# Module_A_IO.net
KiCad netlist of a schematic drawn in Altium Designer
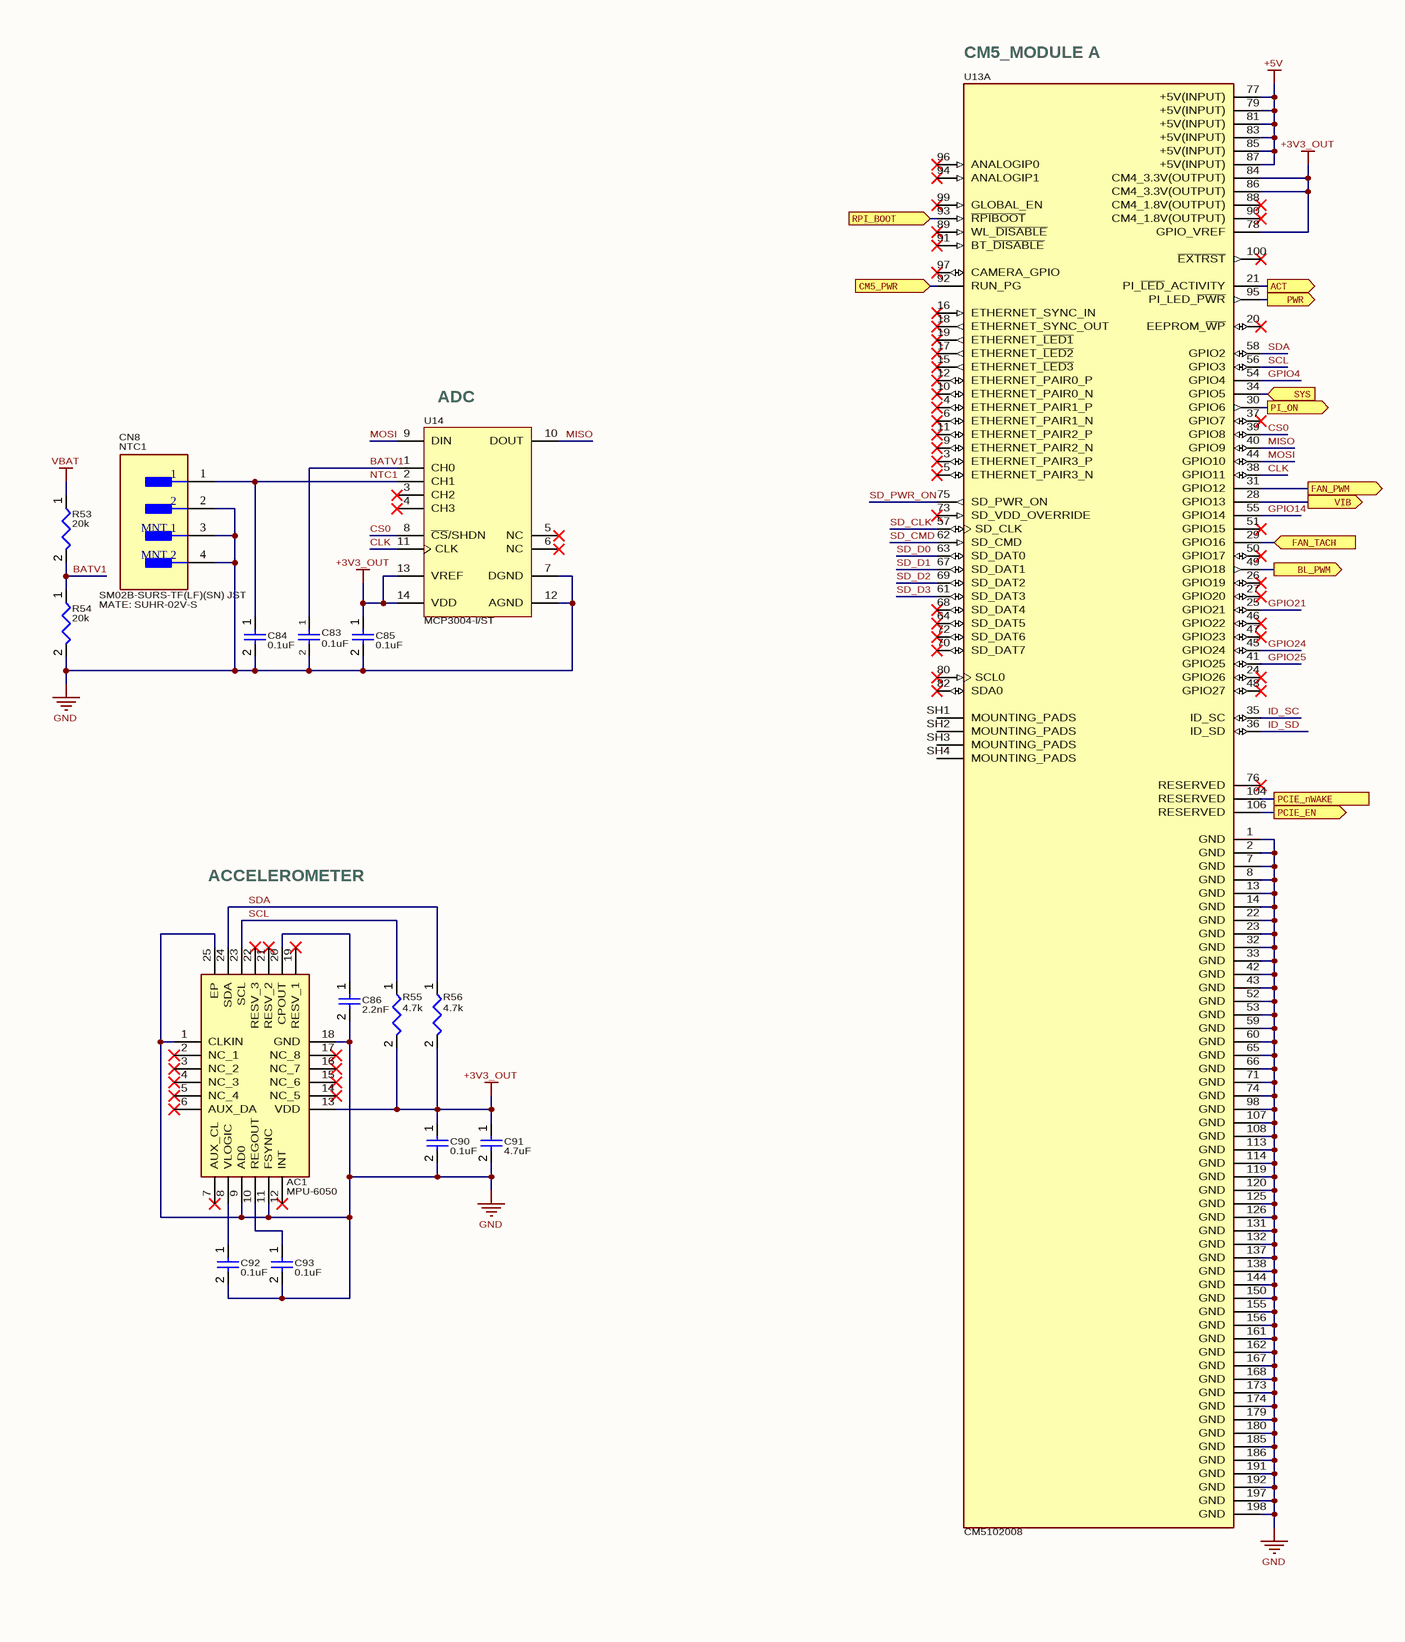
[diagram p0: Module A IO.SchDoc, left]
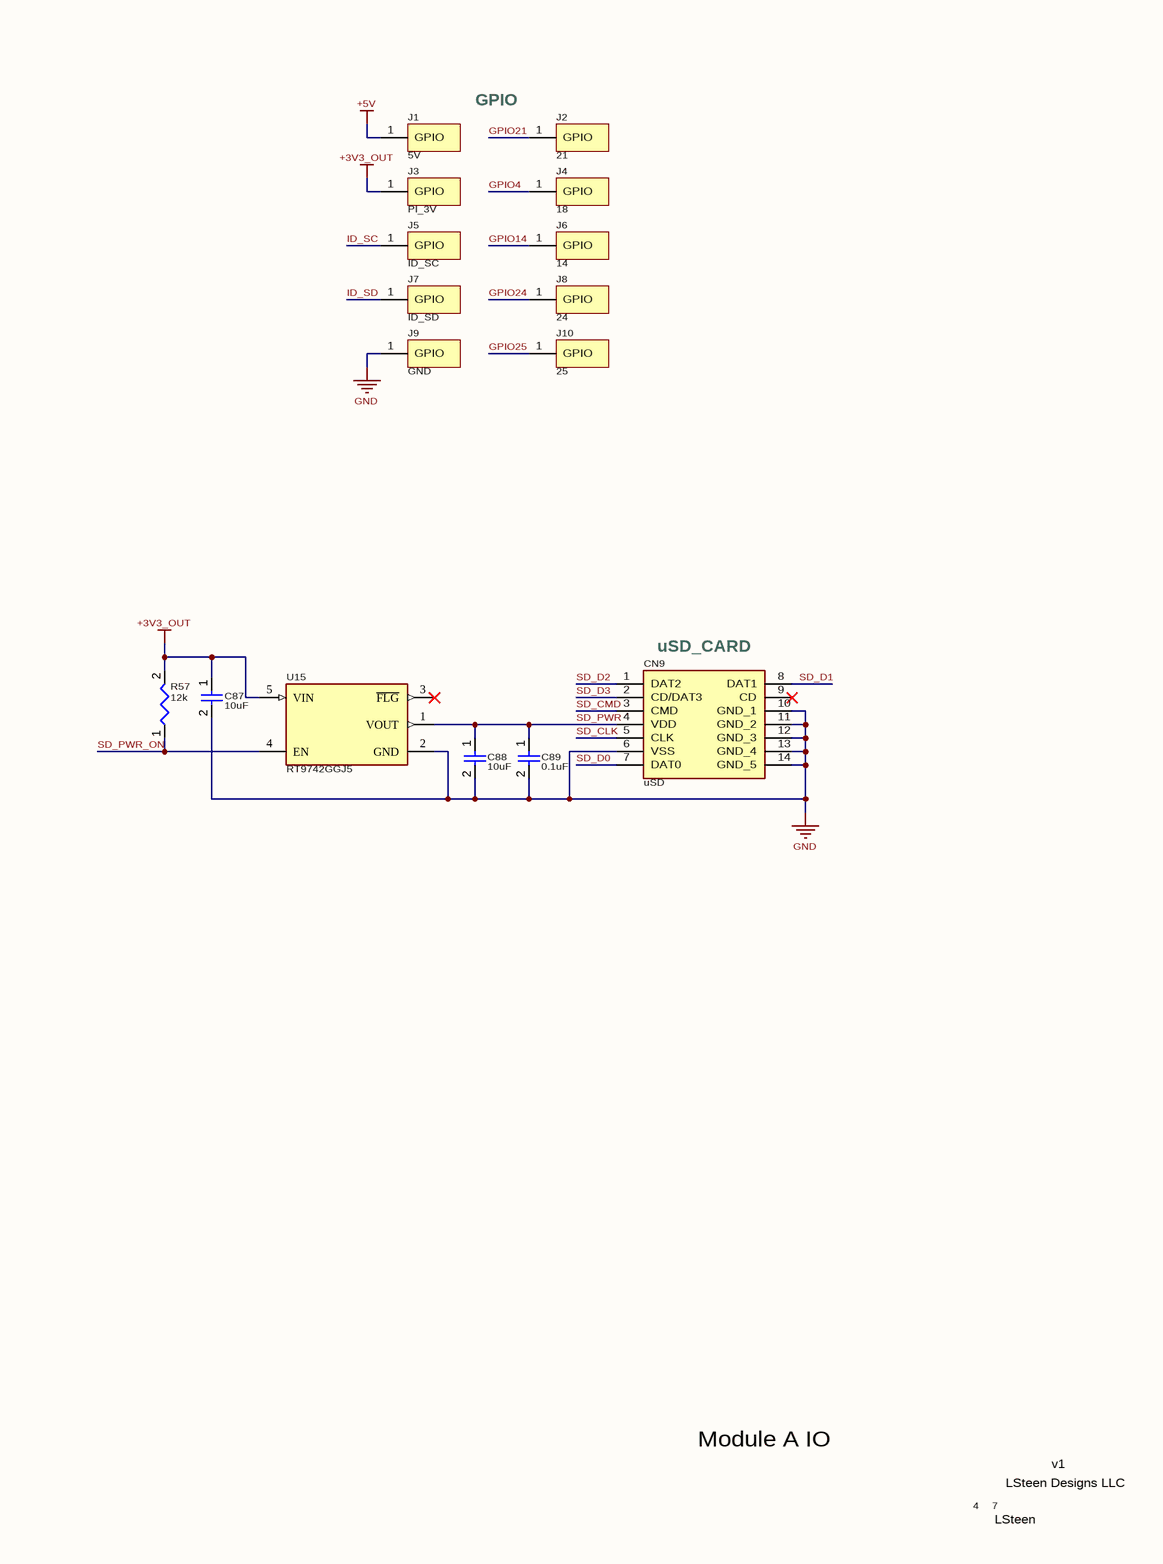
[diagram p1: Module A IO.SchDoc, right]

(export (version "E")
  (design (tool "Eeschema 10.0.6"))
  (components
    (comp (ref "AC1")
      (value "MPU-6050")
      (footprint "SamacSys:MPU6050")
      (description "Integrated Circuit")
      (fields (field (name "MOUSER PART NUMBER") "410-MPU-6050"))
      (libsource (lib "SamacSys") (part "MPU-6050"))
    )
    (comp (ref "C83")
      (value "0.1uF")
      (footprint "SamacSys:CAPC1005X55N")
      (description "C0402")
      (libsource (lib "SamacSys") (part "C0402"))
    )
    (comp (ref "C84")
      (value "0.1uF")
      (footprint "CAPC1005X56X25LL10T15")
      (description "Chip Capacitor, 0.1 uF, +/- 5%, 16 V, 0402 (1005 Metric)")
      (fields (field (name "TOLERANCE") "5%"))
      (libsource (lib "Colorado Technical University") (part "CAP-NP-2"))
    )
    (comp (ref "C85")
      (value "0.1uF")
      (footprint "CAPC1005X56X25LL10T15")
      (description "Chip Capacitor, 0.1 uF, +/- 5%, 16 V, 0402 (1005 Metric)")
      (fields (field (name "TOLERANCE") "5%"))
      (libsource (lib "Colorado Technical University") (part "CAP-NP-2"))
    )
    (comp (ref "C86")
      (value "2.2nF")
      (footprint "CAPC1005X56X25LL10T15")
      (description "Chip Capacitor, 2.2nF, +/- 5%, 16 V, 0402 (1005 Metric)")
      (fields (field (name "TOLERANCE") "5%"))
      (libsource (lib "Colorado Technical University") (part "CAP-NP-2"))
    )
    (comp (ref "C87")
      (value "10uF")
      (footprint "CAPC0603(1608)100_L")
      (description "Chip Capacitor, 10uF +/-20%, 10V, 0603, Thickness 1 mm")
      (fields (field (name "TOLERANCE") "10%"))
      (libsource (lib "Colorado Technical University") (part "CAP-NP-2"))
    )
    (comp (ref "C88")
      (value "10uF")
      (footprint "CAPC0603(1608)100_L")
      (description "Chip Capacitor, 10uF +/-20%, 10V, 0603, Thickness 1 mm")
      (fields (field (name "TOLERANCE") "10%"))
      (libsource (lib "Colorado Technical University") (part "CAP-NP-2"))
    )
    (comp (ref "C89")
      (value "0.1uF")
      (footprint "CAPC1005X56X25LL10T15")
      (description "Chip Capacitor, 0.1 uF, +/- 5%, 16 V, 0402 (1005 Metric)")
      (fields (field (name "TOLERANCE") "5%"))
      (libsource (lib "Colorado Technical University") (part "CAP-NP-2"))
    )
    (comp (ref "C90")
      (value "0.1uF")
      (footprint "CAPC1005X56X25LL10T15")
      (description "Chip Capacitor, 0.1 uF, +/- 5%, 16 V, 0402 (1005 Metric)")
      (fields (field (name "TOLERANCE") "5%"))
      (libsource (lib "Colorado Technical University") (part "CAP-NP-2"))
    )
    (comp (ref "C91")
      (value "4.7uF")
      (footprint "CAPC0603(1608)100_L")
      (description "Chip Capacitor, 4.7uF +/-20%, 10V, 0603, Thickness 1 mm")
      (fields (field (name "TOLERANCE") "10%"))
      (libsource (lib "Colorado Technical University") (part "CAP-NP-2"))
    )
    (comp (ref "C92")
      (value "0.1uF")
      (footprint "CAPC1005X56X25LL10T15")
      (description "Chip Capacitor, 0.1 uF, +/- 5%, 16 V, 0402 (1005 Metric)")
      (fields (field (name "TOLERANCE") "5%"))
      (libsource (lib "Colorado Technical University") (part "CAP-NP-2"))
    )
    (comp (ref "C93")
      (value "0.1uF")
      (footprint "CAPC1005X56X25LL10T15")
      (description "Chip Capacitor, 0.1 uF, +/- 5%, 16 V, 0402 (1005 Metric)")
      (fields (field (name "TOLERANCE") "5%"))
      (libsource (lib "Colorado Technical University") (part "CAP-NP-2"))
    )
    (comp (ref "CN8")
      (value "NTC1")
      (footprint "FP-SM02B-SURS-TF_LF_SN-MFG")
      (description "LCSC_CONN HEADER SMD R/A 2POS 0.8MM")
      (libsource (lib "Altium Content Vault") (part "6ebc6fc72a9fd5a6899c7600f385cff"))
    )
    (comp (ref "CN9")
      (value "uSD")
      (footprint "SamacSys:MSD9A")
      (description "Connector")
      (fields (field (name "MANUFACTURER_PART_NUMBER") "MSD-9-A"))
      (libsource (lib "SamacSys") (part "MSD-9-A"))
    )
    (comp (ref "J1")
      (value "5V")
      (footprint "GPIO")
      (description "AUX_I/O")
      (libsource (lib "Schlib1") (part "GPIO"))
    )
    (comp (ref "J2")
      (value "21")
      (footprint "GPIO")
      (description "AUX_I/O")
      (libsource (lib "Schlib1") (part "GPIO"))
    )
    (comp (ref "J3")
      (value "PI_3V")
      (footprint "GPIO")
      (description "AUX_I/O")
      (libsource (lib "Schlib1") (part "GPIO"))
    )
    (comp (ref "J4")
      (value "18")
      (footprint "GPIO")
      (description "AUX_I/O")
      (libsource (lib "Schlib1") (part "GPIO"))
    )
    (comp (ref "J5")
      (value "ID_SC")
      (footprint "GPIO")
      (description "AUX_I/O")
      (libsource (lib "Schlib1") (part "GPIO"))
    )
    (comp (ref "J6")
      (value "14")
      (footprint "GPIO")
      (description "AUX_I/O")
      (libsource (lib "Schlib1") (part "GPIO"))
    )
    (comp (ref "J7")
      (value "ID_SD")
      (footprint "GPIO")
      (description "AUX_I/O")
      (libsource (lib "Schlib1") (part "GPIO"))
    )
    (comp (ref "J8")
      (value "24")
      (footprint "GPIO")
      (description "AUX_I/O")
      (libsource (lib "Schlib1") (part "GPIO"))
    )
    (comp (ref "J9")
      (value "GND")
      (footprint "GPIO")
      (description "AUX_I/O")
      (libsource (lib "Schlib1") (part "GPIO"))
    )
    (comp (ref "J10")
      (value "25")
      (footprint "GPIO")
      (description "AUX_I/O")
      (libsource (lib "Schlib1") (part "GPIO"))
    )
    (comp (ref "R53")
      (value "20k")
      (footprint "RESC0402(1005)_L")
      (description "Chip Resistor, 20 kOhms, +/-5 %, 63 mW, -55 to 155 degC, 0402")
      (fields (field (name "TOLERANCE") "5%") (field (name "POWER") "63mW"))
      (libsource (lib "Colorado Technical University") (part "RES-2"))
    )
    (comp (ref "R54")
      (value "20k")
      (footprint "RESC0402(1005)_L")
      (description "Chip Resistor, 20 kOhms, +/-5 %, 63 mW, -55 to 155 degC, 0402")
      (fields (field (name "TOLERANCE") "5%") (field (name "POWER") "63mW"))
      (libsource (lib "Colorado Technical University") (part "RES-2"))
    )
    (comp (ref "R55")
      (value "4.7k")
      (footprint "RESC0402(1005)_L")
      (description "Chip Resistor, 4.7 kOhms, +/-5 %, 63 mW, -55 to 155 degC, 0402")
      (fields (field (name "TOLERANCE") "5%") (field (name "POWER") "63mW"))
      (libsource (lib "Colorado Technical University") (part "RES-2"))
    )
    (comp (ref "R56")
      (value "4.7k")
      (footprint "RESC0402(1005)_L")
      (description "Chip Resistor, 4.7 kOhms, +/-5 %, 63 mW, -55 to 155 degC, 0402")
      (fields (field (name "TOLERANCE") "5%") (field (name "POWER") "63mW"))
      (libsource (lib "Colorado Technical University") (part "RES-2"))
    )
    (comp (ref "R57")
      (value "12k")
      (footprint "RESC0402(1005)_L")
      (description "Chip Resistor, 12 kOhms, +/-5 %, 63 mW, -55 to 155 degC, 0402")
      (fields (field (name "TOLERANCE") "5%") (field (name "POWER") "63mW"))
      (libsource (lib "Colorado Technical University") (part "RES-2"))
    )
    (comp (ref "U13")
      (value "CM5102008")
      (footprint "MODULE_CM4102008")
      (description "Raspberry Pi Compute Module 4 with WiFi 2GB RAM 8GB Flash ¦ Raspberry Pi CM4102008")
      (fields (field (name "MF") "Raspberry Pi") (field (name "MP") "CM4102008"))
      (libsource (lib "CM4102008") (part "CM4102008"))
    )
    (comp (ref "U14")
      (value "MCP3004-I/ST")
      (footprint "TSSOP-ST14_M")
      (libsource (lib "Altium Content Vault") (part "CON-ADC-MCP3004-14"))
    )
    (comp (ref "U15")
      (value "RT9742GGJ5")
      (footprint "FP-RT9742GGJ5-IPC_C")
      (description "IC PWR SWTCH N-CHAN 1:1 TSOT23-5")
      (libsource (lib "Altium Content Vault") (part "6b3db7b45087fee8fb60b49bef92a32"))
    )
  )
  (nets
    (net (code "1") (name "+3V3_OUT") (class "Default")
      (node (ref "AC1") (pin "13") (pinfunction "VDD_13") (pintype "passive"))
      (node (ref "C85") (pin "1") (pinfunction "1_1") (pintype "passive"))
      (node (ref "C87") (pin "1") (pinfunction "1_1") (pintype "passive"))
      (node (ref "C90") (pin "1") (pinfunction "1_1") (pintype "passive"))
      (node (ref "C91") (pin "1") (pinfunction "1_1") (pintype "passive"))
      (node (ref "J3") (pin "1") (pinfunction "GPIO_1") (pintype "passive"))
      (node (ref "R55") (pin "2") (pinfunction "2_2") (pintype "passive"))
      (node (ref "R56") (pin "2") (pinfunction "2_2") (pintype "passive"))
      (node (ref "R57") (pin "2") (pinfunction "2_2") (pintype "passive"))
      (node (ref "U13") (pin "78") (pinfunction "GPIO_VREF_78") (pintype "power_in"))
      (node (ref "U13") (pin "84") (pinfunction "CM4_3.3V(OUTPUT)_84") (pintype "power_in"))
      (node (ref "U13") (pin "86") (pinfunction "CM4_3.3V(OUTPUT)_86") (pintype "power_in"))
      (node (ref "U14") (pin "13") (pinfunction "VREF_13") (pintype "passive"))
      (node (ref "U14") (pin "14") (pinfunction "VDD_14") (pintype "power_in"))
      (node (ref "U15") (pin "5") (pinfunction "VIN_5") (pintype "input"))
    )
    (net (code "2") (name "+5V") (class "Default")
      (node (ref "J1") (pin "1") (pinfunction "GPIO_1") (pintype "passive"))
      (node (ref "U13") (pin "77") (pinfunction "+5V(INPUT)_77") (pintype "power_in"))
      (node (ref "U13") (pin "79") (pinfunction "+5V(INPUT)_79") (pintype "power_in"))
      (node (ref "U13") (pin "81") (pinfunction "+5V(INPUT)_81") (pintype "power_in"))
      (node (ref "U13") (pin "83") (pinfunction "+5V(INPUT)_83") (pintype "power_in"))
      (node (ref "U13") (pin "85") (pinfunction "+5V(INPUT)_85") (pintype "power_in"))
      (node (ref "U13") (pin "87") (pinfunction "+5V(INPUT)_87") (pintype "power_in"))
    )
    (net (code "3") (name "/ACT") (class "Default")
      (node (ref "U13") (pin "21") (pinfunction "PI_~{LED}_ACTIVITY_21") (pintype "passive"))
    )
    (net (code "4") (name "/BATV1") (class "Default")
      (node (ref "C83") (pin "1") (pinfunction "1_1") (pintype "passive"))
      (node (ref "R53") (pin "2") (pinfunction "2_2") (pintype "passive"))
      (node (ref "R54") (pin "1") (pinfunction "1_1") (pintype "passive"))
      (node (ref "U14") (pin "1") (pinfunction "CH0_1") (pintype "passive"))
    )
    (net (code "5") (name "/BL_PWM") (class "Default")
      (node (ref "U13") (pin "49") (pinfunction "GPIO18_49") (pintype "output"))
    )
    (net (code "6") (name "/CLK") (class "Default")
      (node (ref "U13") (pin "38") (pinfunction "GPIO11_38") (pintype "bidirectional"))
      (node (ref "U14") (pin "11") (pinfunction "CLK_11") (pintype "passive"))
    )
    (net (code "7") (name "/CM5_PWR") (class "Default")
      (node (ref "U13") (pin "92") (pinfunction "RUN_PG_92") (pintype "passive"))
    )
    (net (code "8") (name "/CS0") (class "Default")
      (node (ref "U13") (pin "39") (pinfunction "GPIO8_39") (pintype "bidirectional"))
      (node (ref "U14") (pin "8") (pinfunction "~{CS}/SHDN_8") (pintype "passive"))
    )
    (net (code "9") (name "/FAN_PWM") (class "Default")
      (node (ref "U13") (pin "31") (pinfunction "GPIO12_31") (pintype "passive"))
    )
    (net (code "10") (name "/FAN_TACH") (class "Default")
      (node (ref "U13") (pin "29") (pinfunction "GPIO16_29") (pintype "passive"))
    )
    (net (code "11") (name "/GPIO4") (class "Default")
      (node (ref "J4") (pin "1") (pinfunction "GPIO_1") (pintype "passive"))
      (node (ref "U13") (pin "54") (pinfunction "GPIO4_54") (pintype "passive"))
    )
    (net (code "12") (name "/GPIO14") (class "Default")
      (node (ref "J6") (pin "1") (pinfunction "GPIO_1") (pintype "passive"))
      (node (ref "U13") (pin "55") (pinfunction "GPIO14_55") (pintype "passive"))
    )
    (net (code "13") (name "/GPIO21") (class "Default")
      (node (ref "J2") (pin "1") (pinfunction "GPIO_1") (pintype "passive"))
      (node (ref "U13") (pin "25") (pinfunction "GPIO21_25") (pintype "bidirectional"))
    )
    (net (code "14") (name "/GPIO24") (class "Default")
      (node (ref "J8") (pin "1") (pinfunction "GPIO_1") (pintype "passive"))
      (node (ref "U13") (pin "45") (pinfunction "GPIO24_45") (pintype "bidirectional"))
    )
    (net (code "15") (name "/GPIO25") (class "Default")
      (node (ref "J10") (pin "1") (pinfunction "GPIO_1") (pintype "passive"))
      (node (ref "U13") (pin "41") (pinfunction "GPIO25_41") (pintype "bidirectional"))
    )
    (net (code "16") (name "/ID_SC") (class "Default")
      (node (ref "J5") (pin "1") (pinfunction "GPIO_1") (pintype "passive"))
      (node (ref "U13") (pin "35") (pinfunction "ID_SC_35") (pintype "bidirectional"))
    )
    (net (code "17") (name "/ID_SD") (class "Default")
      (node (ref "J7") (pin "1") (pinfunction "GPIO_1") (pintype "passive"))
      (node (ref "U13") (pin "36") (pinfunction "ID_SD_36") (pintype "bidirectional"))
    )
    (net (code "18") (name "/MISO") (class "Default")
      (node (ref "U13") (pin "40") (pinfunction "GPIO9_40") (pintype "bidirectional"))
      (node (ref "U14") (pin "10") (pinfunction "DOUT_10") (pintype "tri_state"))
    )
    (net (code "19") (name "/MOSI") (class "Default")
      (node (ref "U13") (pin "44") (pinfunction "GPIO10_44") (pintype "bidirectional"))
      (node (ref "U14") (pin "9") (pinfunction "DIN_9") (pintype "passive"))
    )
    (net (code "20") (name "/NTC1") (class "Default")
      (node (ref "C84") (pin "1") (pinfunction "1_1") (pintype "passive"))
      (node (ref "CN8") (pin "1") (pinfunction "1_1") (pintype "passive"))
      (node (ref "U14") (pin "2") (pinfunction "CH1_2") (pintype "passive"))
    )
    (net (code "21") (name "/PCIE_EN") (class "Default")
      (node (ref "U13") (pin "106") (pinfunction "RESERVED_106") (pintype "passive"))
    )
    (net (code "22") (name "/PCIE_nWAKE") (class "Default")
      (node (ref "U13") (pin "104") (pinfunction "RESERVED_104") (pintype "passive"))
    )
    (net (code "23") (name "/PI_ON") (class "Default")
      (node (ref "U13") (pin "30") (pinfunction "GPIO6_30") (pintype "output"))
    )
    (net (code "24") (name "/PWR") (class "Default")
      (node (ref "U13") (pin "95") (pinfunction "PI_LED_~{PWR}_95") (pintype "output"))
    )
    (net (code "25") (name "/RPI_BOOT") (class "Default")
      (node (ref "U13") (pin "93") (pinfunction "~{RPIBOOT}_93") (pintype "input"))
    )
    (net (code "26") (name "/SCL") (class "Default")
      (node (ref "AC1") (pin "23") (pinfunction "SCL_23") (pintype "passive"))
      (node (ref "R55") (pin "1") (pinfunction "1_1") (pintype "passive"))
      (node (ref "U13") (pin "56") (pinfunction "GPIO3_56") (pintype "bidirectional"))
    )
    (net (code "27") (name "/SDA") (class "Default")
      (node (ref "AC1") (pin "24") (pinfunction "SDA_24") (pintype "passive"))
      (node (ref "R56") (pin "1") (pinfunction "1_1") (pintype "passive"))
      (node (ref "U13") (pin "58") (pinfunction "GPIO2_58") (pintype "bidirectional"))
    )
    (net (code "28") (name "/SD_CLK") (class "Default")
      (node (ref "CN9") (pin "5") (pinfunction "CLK_5") (pintype "passive"))
      (node (ref "U13") (pin "57") (pinfunction "SD_CLK_57") (pintype "bidirectional"))
    )
    (net (code "29") (name "/SD_CMD") (class "Default")
      (node (ref "CN9") (pin "3") (pinfunction "CMD_3") (pintype "passive"))
      (node (ref "U13") (pin "62") (pinfunction "SD_CMD_62") (pintype "input"))
    )
    (net (code "30") (name "/SD_D0") (class "Default")
      (node (ref "CN9") (pin "7") (pinfunction "DAT0_7") (pintype "passive"))
      (node (ref "U13") (pin "63") (pinfunction "SD_DAT0_63") (pintype "bidirectional"))
    )
    (net (code "31") (name "/SD_D1") (class "Default")
      (node (ref "CN9") (pin "8") (pinfunction "DAT1_8") (pintype "passive"))
      (node (ref "U13") (pin "67") (pinfunction "SD_DAT1_67") (pintype "bidirectional"))
    )
    (net (code "32") (name "/SD_D2") (class "Default")
      (node (ref "CN9") (pin "1") (pinfunction "DAT2_1") (pintype "passive"))
      (node (ref "U13") (pin "69") (pinfunction "SD_DAT2_69") (pintype "bidirectional"))
    )
    (net (code "33") (name "/SD_D3") (class "Default")
      (node (ref "CN9") (pin "2") (pinfunction "CD/DAT3_2") (pintype "passive"))
      (node (ref "U13") (pin "61") (pinfunction "SD_DAT3_61") (pintype "bidirectional"))
    )
    (net (code "34") (name "/SD_PWR") (class "Default")
      (node (ref "C88") (pin "1") (pinfunction "1_1") (pintype "passive"))
      (node (ref "C89") (pin "1") (pinfunction "1_1") (pintype "passive"))
      (node (ref "CN9") (pin "4") (pinfunction "VDD_4") (pintype "passive"))
      (node (ref "U15") (pin "1") (pinfunction "VOUT_1") (pintype "output"))
    )
    (net (code "35") (name "/SD_PWR_ON") (class "Default")
      (node (ref "R57") (pin "1") (pinfunction "1_1") (pintype "passive"))
      (node (ref "U13") (pin "75") (pinfunction "SD_PWR_ON_75") (pintype "output"))
      (node (ref "U15") (pin "4") (pinfunction "EN_4") (pintype "passive"))
    )
    (net (code "36") (name "/SYS") (class "Default")
      (node (ref "U13") (pin "34") (pinfunction "GPIO5_34") (pintype "passive"))
    )
    (net (code "37") (name "/VIB") (class "Default")
      (node (ref "U13") (pin "28") (pinfunction "GPIO13_28") (pintype "passive"))
    )
    (net (code "38") (name "GND") (class "Default")
      (node (ref "AC1") (pin "1") (pinfunction "CLKIN_1") (pintype "passive"))
      (node (ref "AC1") (pin "11") (pinfunction "FSYNC_11") (pintype "passive"))
      (node (ref "AC1") (pin "18") (pinfunction "GND_18") (pintype "passive"))
      (node (ref "AC1") (pin "25") (pinfunction "EP_25") (pintype "passive"))
      (node (ref "AC1") (pin "9") (pinfunction "AD0_9") (pintype "passive"))
      (node (ref "C83") (pin "2") (pinfunction "2_2") (pintype "passive"))
      (node (ref "C84") (pin "2") (pinfunction "2_2") (pintype "passive"))
      (node (ref "C85") (pin "2") (pinfunction "2_2") (pintype "passive"))
      (node (ref "C86") (pin "2") (pinfunction "2_2") (pintype "passive"))
      (node (ref "C87") (pin "2") (pinfunction "2_2") (pintype "passive"))
      (node (ref "C88") (pin "2") (pinfunction "2_2") (pintype "passive"))
      (node (ref "C89") (pin "2") (pinfunction "2_2") (pintype "passive"))
      (node (ref "C90") (pin "2") (pinfunction "2_2") (pintype "passive"))
      (node (ref "C91") (pin "2") (pinfunction "2_2") (pintype "passive"))
      (node (ref "C92") (pin "2") (pinfunction "2_2") (pintype "passive"))
      (node (ref "C93") (pin "2") (pinfunction "2_2") (pintype "passive"))
      (node (ref "CN8") (pin "2") (pinfunction "2_2") (pintype "passive"))
      (node (ref "CN8") (pin "3") (pinfunction "MNT_1_3") (pintype "passive"))
      (node (ref "CN8") (pin "4") (pinfunction "MNT_2_4") (pintype "passive"))
      (node (ref "CN9") (pin "10") (pinfunction "GND_1_10") (pintype "passive"))
      (node (ref "CN9") (pin "11") (pinfunction "GND_2_11") (pintype "passive"))
      (node (ref "CN9") (pin "12") (pinfunction "GND_3_12") (pintype "passive"))
      (node (ref "CN9") (pin "13") (pinfunction "GND_4_13") (pintype "passive"))
      (node (ref "CN9") (pin "14") (pinfunction "GND_5_14") (pintype "passive"))
      (node (ref "CN9") (pin "6") (pinfunction "VSS_6") (pintype "passive"))
      (node (ref "J9") (pin "1") (pinfunction "GPIO_1") (pintype "passive"))
      (node (ref "R54") (pin "2") (pinfunction "2_2") (pintype "passive"))
      (node (ref "U13") (pin "1") (pinfunction "GND_1") (pintype "power_in"))
      (node (ref "U13") (pin "107") (pinfunction "GND_107") (pintype "power_in"))
      (node (ref "U13") (pin "108") (pinfunction "GND_108") (pintype "power_in"))
      (node (ref "U13") (pin "113") (pinfunction "GND_113") (pintype "power_in"))
      (node (ref "U13") (pin "114") (pinfunction "GND_114") (pintype "power_in"))
      (node (ref "U13") (pin "119") (pinfunction "GND_119") (pintype "power_in"))
      (node (ref "U13") (pin "120") (pinfunction "GND_120") (pintype "power_in"))
      (node (ref "U13") (pin "125") (pinfunction "GND_125") (pintype "power_in"))
      (node (ref "U13") (pin "126") (pinfunction "GND_126") (pintype "power_in"))
      (node (ref "U13") (pin "13") (pinfunction "GND_13") (pintype "power_in"))
      (node (ref "U13") (pin "131") (pinfunction "GND_131") (pintype "power_in"))
      (node (ref "U13") (pin "132") (pinfunction "GND_132") (pintype "power_in"))
      (node (ref "U13") (pin "137") (pinfunction "GND_137") (pintype "power_in"))
      (node (ref "U13") (pin "138") (pinfunction "GND_138") (pintype "power_in"))
      (node (ref "U13") (pin "14") (pinfunction "GND_14") (pintype "power_in"))
      (node (ref "U13") (pin "144") (pinfunction "GND_144") (pintype "power_in"))
      (node (ref "U13") (pin "150") (pinfunction "GND_150") (pintype "power_in"))
      (node (ref "U13") (pin "155") (pinfunction "GND_155") (pintype "power_in"))
      (node (ref "U13") (pin "156") (pinfunction "GND_156") (pintype "power_in"))
      (node (ref "U13") (pin "161") (pinfunction "GND_161") (pintype "power_in"))
      (node (ref "U13") (pin "162") (pinfunction "GND_162") (pintype "power_in"))
      (node (ref "U13") (pin "167") (pinfunction "GND_167") (pintype "power_in"))
      (node (ref "U13") (pin "168") (pinfunction "GND_168") (pintype "power_in"))
      (node (ref "U13") (pin "173") (pinfunction "GND_173") (pintype "power_in"))
      (node (ref "U13") (pin "174") (pinfunction "GND_174") (pintype "power_in"))
      (node (ref "U13") (pin "179") (pinfunction "GND_179") (pintype "power_in"))
      (node (ref "U13") (pin "180") (pinfunction "GND_180") (pintype "power_in"))
      (node (ref "U13") (pin "185") (pinfunction "GND_185") (pintype "power_in"))
      (node (ref "U13") (pin "186") (pinfunction "GND_186") (pintype "power_in"))
      (node (ref "U13") (pin "191") (pinfunction "GND_191") (pintype "power_in"))
      (node (ref "U13") (pin "192") (pinfunction "GND_192") (pintype "power_in"))
      (node (ref "U13") (pin "197") (pinfunction "GND_197") (pintype "power_in"))
      (node (ref "U13") (pin "198") (pinfunction "GND_198") (pintype "power_in"))
      (node (ref "U13") (pin "2") (pinfunction "GND_2") (pintype "power_in"))
      (node (ref "U13") (pin "22") (pinfunction "GND_22") (pintype "power_in"))
      (node (ref "U13") (pin "23") (pinfunction "GND_23") (pintype "power_in"))
      (node (ref "U13") (pin "32") (pinfunction "GND_32") (pintype "power_in"))
      (node (ref "U13") (pin "33") (pinfunction "GND_33") (pintype "power_in"))
      (node (ref "U13") (pin "42") (pinfunction "GND_42") (pintype "power_in"))
      (node (ref "U13") (pin "43") (pinfunction "GND_43") (pintype "power_in"))
      (node (ref "U13") (pin "52") (pinfunction "GND_52") (pintype "power_in"))
      (node (ref "U13") (pin "53") (pinfunction "GND_53") (pintype "power_in"))
      (node (ref "U13") (pin "59") (pinfunction "GND_59") (pintype "power_in"))
      (node (ref "U13") (pin "60") (pinfunction "GND_60") (pintype "power_in"))
      (node (ref "U13") (pin "65") (pinfunction "GND_65") (pintype "power_in"))
      (node (ref "U13") (pin "66") (pinfunction "GND_66") (pintype "power_in"))
      (node (ref "U13") (pin "7") (pinfunction "GND_7") (pintype "power_in"))
      (node (ref "U13") (pin "71") (pinfunction "GND_71") (pintype "power_in"))
      (node (ref "U13") (pin "74") (pinfunction "GND_74") (pintype "power_in"))
      (node (ref "U13") (pin "8") (pinfunction "GND_8") (pintype "power_in"))
      (node (ref "U13") (pin "98") (pinfunction "GND_98") (pintype "power_in"))
      (node (ref "U14") (pin "12") (pinfunction "AGND_12") (pintype "power_in"))
      (node (ref "U14") (pin "7") (pinfunction "DGND_7") (pintype "power_in"))
      (node (ref "U15") (pin "2") (pinfunction "GND_2") (pintype "power_in"))
    )
    (net (code "39") (name "Net-(AC1-CPOUT)") (class "Default")
      (node (ref "AC1") (pin "20") (pinfunction "CPOUT_20") (pintype "passive"))
      (node (ref "C86") (pin "1") (pinfunction "1_1") (pintype "passive"))
    )
    (net (code "40") (name "Net-(AC1-REGOUT)") (class "Default")
      (node (ref "AC1") (pin "10") (pinfunction "REGOUT_10") (pintype "passive"))
      (node (ref "C93") (pin "1") (pinfunction "1_1") (pintype "passive"))
    )
    (net (code "41") (name "Net-(AC1-VLOGIC)") (class "Default")
      (node (ref "AC1") (pin "8") (pinfunction "VLOGIC_8") (pintype "passive"))
      (node (ref "C92") (pin "1") (pinfunction "1_1") (pintype "passive"))
    )
    (net (code "42") (name "VBAT") (class "Default")
      (node (ref "R53") (pin "1") (pinfunction "1_1") (pintype "passive"))
    )
    (net (code "43") (name "unconnected-(AC1-AUX_CL-Pad7)") (class "Default")
      (node (ref "AC1") (pin "7") (pinfunction "AUX_CL_7") (pintype "passive+no_connect"))
    )
    (net (code "44") (name "unconnected-(AC1-AUX_DA-Pad6)") (class "Default")
      (node (ref "AC1") (pin "6") (pinfunction "AUX_DA_6") (pintype "passive+no_connect"))
    )
    (net (code "45") (name "unconnected-(AC1-INT-Pad12)") (class "Default")
      (node (ref "AC1") (pin "12") (pinfunction "INT_12") (pintype "passive+no_connect"))
    )
    (net (code "46") (name "unconnected-(AC1-NC_1-Pad2)") (class "Default")
      (node (ref "AC1") (pin "2") (pinfunction "NC_1_2") (pintype "passive+no_connect"))
    )
    (net (code "47") (name "unconnected-(AC1-NC_2-Pad3)") (class "Default")
      (node (ref "AC1") (pin "3") (pinfunction "NC_2_3") (pintype "passive+no_connect"))
    )
    (net (code "48") (name "unconnected-(AC1-NC_3-Pad4)") (class "Default")
      (node (ref "AC1") (pin "4") (pinfunction "NC_3_4") (pintype "passive+no_connect"))
    )
    (net (code "49") (name "unconnected-(AC1-NC_4-Pad5)") (class "Default")
      (node (ref "AC1") (pin "5") (pinfunction "NC_4_5") (pintype "passive+no_connect"))
    )
    (net (code "50") (name "unconnected-(AC1-NC_5-Pad14)") (class "Default")
      (node (ref "AC1") (pin "14") (pinfunction "NC_5_14") (pintype "passive+no_connect"))
    )
    (net (code "51") (name "unconnected-(AC1-NC_6-Pad15)") (class "Default")
      (node (ref "AC1") (pin "15") (pinfunction "NC_6_15") (pintype "passive+no_connect"))
    )
    (net (code "52") (name "unconnected-(AC1-NC_7-Pad16)") (class "Default")
      (node (ref "AC1") (pin "16") (pinfunction "NC_7_16") (pintype "passive+no_connect"))
    )
    (net (code "53") (name "unconnected-(AC1-NC_8-Pad17)") (class "Default")
      (node (ref "AC1") (pin "17") (pinfunction "NC_8_17") (pintype "passive+no_connect"))
    )
    (net (code "54") (name "unconnected-(AC1-RESV_1-Pad19)") (class "Default")
      (node (ref "AC1") (pin "19") (pinfunction "RESV_1_19") (pintype "passive+no_connect"))
    )
    (net (code "55") (name "unconnected-(AC1-RESV_2-Pad21)") (class "Default")
      (node (ref "AC1") (pin "21") (pinfunction "RESV_2_21") (pintype "passive+no_connect"))
    )
    (net (code "56") (name "unconnected-(AC1-RESV_3-Pad22)") (class "Default")
      (node (ref "AC1") (pin "22") (pinfunction "RESV_3_22") (pintype "passive+no_connect"))
    )
    (net (code "57") (name "unconnected-(CN9-CD-Pad9)") (class "Default")
      (node (ref "CN9") (pin "9") (pinfunction "CD_9") (pintype "passive+no_connect"))
    )
    (net (code "58") (name "unconnected-(U13A-ANALOGIP0-Pad96)") (class "Default")
      (node (ref "U13") (pin "96") (pinfunction "ANALOGIP0_96") (pintype "input+no_connect"))
    )
    (net (code "59") (name "unconnected-(U13A-ANALOGIP1-Pad94)") (class "Default")
      (node (ref "U13") (pin "94") (pinfunction "ANALOGIP1_94") (pintype "input+no_connect"))
    )
    (net (code "60") (name "unconnected-(U13A-BT_~{DISABLE}-Pad91)") (class "Default")
      (node (ref "U13") (pin "91") (pinfunction "BT_~{DISABLE}_91") (pintype "input+no_connect"))
    )
    (net (code "61") (name "unconnected-(U13A-CAMERA_GPIO-Pad97)") (class "Default")
      (node (ref "U13") (pin "97") (pinfunction "CAMERA_GPIO_97") (pintype "bidirectional+no_connect"))
    )
    (net (code "62") (name "unconnected-(U13A-CM4_1.8V(OUTPUT)-Pad88)") (class "Default")
      (node (ref "U13") (pin "88") (pinfunction "CM4_1.8V(OUTPUT)_88") (pintype "power_in+no_connect"))
    )
    (net (code "63") (name "unconnected-(U13A-CM4_1.8V(OUTPUT)-Pad90)") (class "Default")
      (node (ref "U13") (pin "90") (pinfunction "CM4_1.8V(OUTPUT)_90") (pintype "power_in+no_connect"))
    )
    (net (code "64") (name "unconnected-(U13A-EEPROM_~{WP}-Pad20)") (class "Default")
      (node (ref "U13") (pin "20") (pinfunction "EEPROM_~{WP}_20") (pintype "bidirectional+no_connect"))
    )
    (net (code "65") (name "unconnected-(U13A-ETHERNET_PAIR0_N-Pad10)") (class "Default")
      (node (ref "U13") (pin "10") (pinfunction "ETHERNET_PAIR0_N_10") (pintype "bidirectional+no_connect"))
    )
    (net (code "66") (name "unconnected-(U13A-ETHERNET_PAIR0_P-Pad12)") (class "Default")
      (node (ref "U13") (pin "12") (pinfunction "ETHERNET_PAIR0_P_12") (pintype "bidirectional+no_connect"))
    )
    (net (code "67") (name "unconnected-(U13A-ETHERNET_PAIR1_N-Pad6)") (class "Default")
      (node (ref "U13") (pin "6") (pinfunction "ETHERNET_PAIR1_N_6") (pintype "bidirectional+no_connect"))
    )
    (net (code "68") (name "unconnected-(U13A-ETHERNET_PAIR1_P-Pad4)") (class "Default")
      (node (ref "U13") (pin "4") (pinfunction "ETHERNET_PAIR1_P_4") (pintype "bidirectional+no_connect"))
    )
    (net (code "69") (name "unconnected-(U13A-ETHERNET_PAIR2_N-Pad9)") (class "Default")
      (node (ref "U13") (pin "9") (pinfunction "ETHERNET_PAIR2_N_9") (pintype "bidirectional+no_connect"))
    )
    (net (code "70") (name "unconnected-(U13A-ETHERNET_PAIR2_P-Pad11)") (class "Default")
      (node (ref "U13") (pin "11") (pinfunction "ETHERNET_PAIR2_P_11") (pintype "bidirectional+no_connect"))
    )
    (net (code "71") (name "unconnected-(U13A-ETHERNET_PAIR3_N-Pad5)") (class "Default")
      (node (ref "U13") (pin "5") (pinfunction "ETHERNET_PAIR3_N_5") (pintype "bidirectional+no_connect"))
    )
    (net (code "72") (name "unconnected-(U13A-ETHERNET_PAIR3_P-Pad3)") (class "Default")
      (node (ref "U13") (pin "3") (pinfunction "ETHERNET_PAIR3_P_3") (pintype "bidirectional+no_connect"))
    )
    (net (code "73") (name "unconnected-(U13A-ETHERNET_SYNC_IN-Pad16)") (class "Default")
      (node (ref "U13") (pin "16") (pinfunction "ETHERNET_SYNC_IN_16") (pintype "input+no_connect"))
    )
    (net (code "74") (name "unconnected-(U13A-ETHERNET_SYNC_OUT-Pad18)") (class "Default")
      (node (ref "U13") (pin "18") (pinfunction "ETHERNET_SYNC_OUT_18") (pintype "output+no_connect"))
    )
    (net (code "75") (name "unconnected-(U13A-ETHERNET_~{LED1}-Pad19)") (class "Default")
      (node (ref "U13") (pin "19") (pinfunction "ETHERNET_~{LED1}_19") (pintype "output+no_connect"))
    )
    (net (code "76") (name "unconnected-(U13A-ETHERNET_~{LED2}-Pad17)") (class "Default")
      (node (ref "U13") (pin "17") (pinfunction "ETHERNET_~{LED2}_17") (pintype "output+no_connect"))
    )
    (net (code "77") (name "unconnected-(U13A-ETHERNET_~{LED3}-Pad15)") (class "Default")
      (node (ref "U13") (pin "15") (pinfunction "ETHERNET_~{LED3}_15") (pintype "output+no_connect"))
    )
    (net (code "78") (name "unconnected-(U13A-GLOBAL_EN-Pad99)") (class "Default")
      (node (ref "U13") (pin "99") (pinfunction "GLOBAL_EN_99") (pintype "input+no_connect"))
    )
    (net (code "79") (name "unconnected-(U13A-GPIO7-Pad37)") (class "Default")
      (node (ref "U13") (pin "37") (pinfunction "GPIO7_37") (pintype "bidirectional+no_connect"))
    )
    (net (code "80") (name "unconnected-(U13A-GPIO15-Pad51)") (class "Default")
      (node (ref "U13") (pin "51") (pinfunction "GPIO15_51") (pintype "passive+no_connect"))
    )
    (net (code "81") (name "unconnected-(U13A-GPIO17-Pad50)") (class "Default")
      (node (ref "U13") (pin "50") (pinfunction "GPIO17_50") (pintype "bidirectional+no_connect"))
    )
    (net (code "82") (name "unconnected-(U13A-GPIO19-Pad26)") (class "Default")
      (node (ref "U13") (pin "26") (pinfunction "GPIO19_26") (pintype "bidirectional+no_connect"))
    )
    (net (code "83") (name "unconnected-(U13A-GPIO20-Pad27)") (class "Default")
      (node (ref "U13") (pin "27") (pinfunction "GPIO20_27") (pintype "bidirectional+no_connect"))
    )
    (net (code "84") (name "unconnected-(U13A-GPIO22-Pad46)") (class "Default")
      (node (ref "U13") (pin "46") (pinfunction "GPIO22_46") (pintype "bidirectional+no_connect"))
    )
    (net (code "85") (name "unconnected-(U13A-GPIO23-Pad47)") (class "Default")
      (node (ref "U13") (pin "47") (pinfunction "GPIO23_47") (pintype "bidirectional+no_connect"))
    )
    (net (code "86") (name "unconnected-(U13A-GPIO26-Pad24)") (class "Default")
      (node (ref "U13") (pin "24") (pinfunction "GPIO26_24") (pintype "bidirectional+no_connect"))
    )
    (net (code "87") (name "unconnected-(U13A-GPIO27-Pad48)") (class "Default")
      (node (ref "U13") (pin "48") (pinfunction "GPIO27_48") (pintype "bidirectional+no_connect"))
    )
    (net (code "88") (name "unconnected-(U13A-MOUNTING_PADS-PadSH1)") (class "Default")
      (node (ref "U13") (pin "SH1") (pinfunction "MOUNTING_PADS_SH1") (pintype "passive"))
    )
    (net (code "89") (name "unconnected-(U13A-MOUNTING_PADS-PadSH2)") (class "Default")
      (node (ref "U13") (pin "SH2") (pinfunction "MOUNTING_PADS_SH2") (pintype "passive"))
    )
    (net (code "90") (name "unconnected-(U13A-MOUNTING_PADS-PadSH3)") (class "Default")
      (node (ref "U13") (pin "SH3") (pinfunction "MOUNTING_PADS_SH3") (pintype "passive"))
    )
    (net (code "91") (name "unconnected-(U13A-MOUNTING_PADS-PadSH4)") (class "Default")
      (node (ref "U13") (pin "SH4") (pinfunction "MOUNTING_PADS_SH4") (pintype "passive"))
    )
    (net (code "92") (name "unconnected-(U13A-RESERVED-Pad76)") (class "Default")
      (node (ref "U13") (pin "76") (pinfunction "RESERVED_76") (pintype "passive+no_connect"))
    )
    (net (code "93") (name "unconnected-(U13A-SCL0-Pad80)") (class "Default")
      (node (ref "U13") (pin "80") (pinfunction "SCL0_80") (pintype "input+no_connect"))
    )
    (net (code "94") (name "unconnected-(U13A-SDA0-Pad82)") (class "Default")
      (node (ref "U13") (pin "82") (pinfunction "SDA0_82") (pintype "bidirectional+no_connect"))
    )
    (net (code "95") (name "unconnected-(U13A-SD_DAT4-Pad68)") (class "Default")
      (node (ref "U13") (pin "68") (pinfunction "SD_DAT4_68") (pintype "bidirectional+no_connect"))
    )
    (net (code "96") (name "unconnected-(U13A-SD_DAT5-Pad64)") (class "Default")
      (node (ref "U13") (pin "64") (pinfunction "SD_DAT5_64") (pintype "bidirectional+no_connect"))
    )
    (net (code "97") (name "unconnected-(U13A-SD_DAT6-Pad72)") (class "Default")
      (node (ref "U13") (pin "72") (pinfunction "SD_DAT6_72") (pintype "bidirectional+no_connect"))
    )
    (net (code "98") (name "unconnected-(U13A-SD_DAT7-Pad70)") (class "Default")
      (node (ref "U13") (pin "70") (pinfunction "SD_DAT7_70") (pintype "bidirectional+no_connect"))
    )
    (net (code "99") (name "unconnected-(U13A-SD_VDD_OVERRIDE-Pad73)") (class "Default")
      (node (ref "U13") (pin "73") (pinfunction "SD_VDD_OVERRIDE_73") (pintype "input+no_connect"))
    )
    (net (code "100") (name "unconnected-(U13A-WL_~{DISABLE}-Pad89)") (class "Default")
      (node (ref "U13") (pin "89") (pinfunction "WL_~{DISABLE}_89") (pintype "input+no_connect"))
    )
    (net (code "101") (name "unconnected-(U13A-~{EXTRST}-Pad100)") (class "Default")
      (node (ref "U13") (pin "100") (pinfunction "~{EXTRST}_100") (pintype "output+no_connect"))
    )
    (net (code "102") (name "unconnected-(U14-CH2-Pad3)") (class "Default")
      (node (ref "U14") (pin "3") (pinfunction "CH2_3") (pintype "passive+no_connect"))
    )
    (net (code "103") (name "unconnected-(U14-CH3-Pad4)") (class "Default")
      (node (ref "U14") (pin "4") (pinfunction "CH3_4") (pintype "passive+no_connect"))
    )
    (net (code "104") (name "unconnected-(U14-NC-Pad5)") (class "Default")
      (node (ref "U14") (pin "5") (pinfunction "NC_5") (pintype "passive+no_connect"))
    )
    (net (code "105") (name "unconnected-(U14-NC-Pad6)") (class "Default")
      (node (ref "U14") (pin "6") (pinfunction "NC_6") (pintype "passive+no_connect"))
    )
    (net (code "106") (name "unconnected-(U15-~{FLG}-Pad3)") (class "Default")
      (node (ref "U15") (pin "3") (pinfunction "~{FLG}_3") (pintype "output+no_connect"))
    )
  )
)
